# EEGAmp_SMT_MountHole.net
KiCad netlist of a schematic drawn in EAGLE
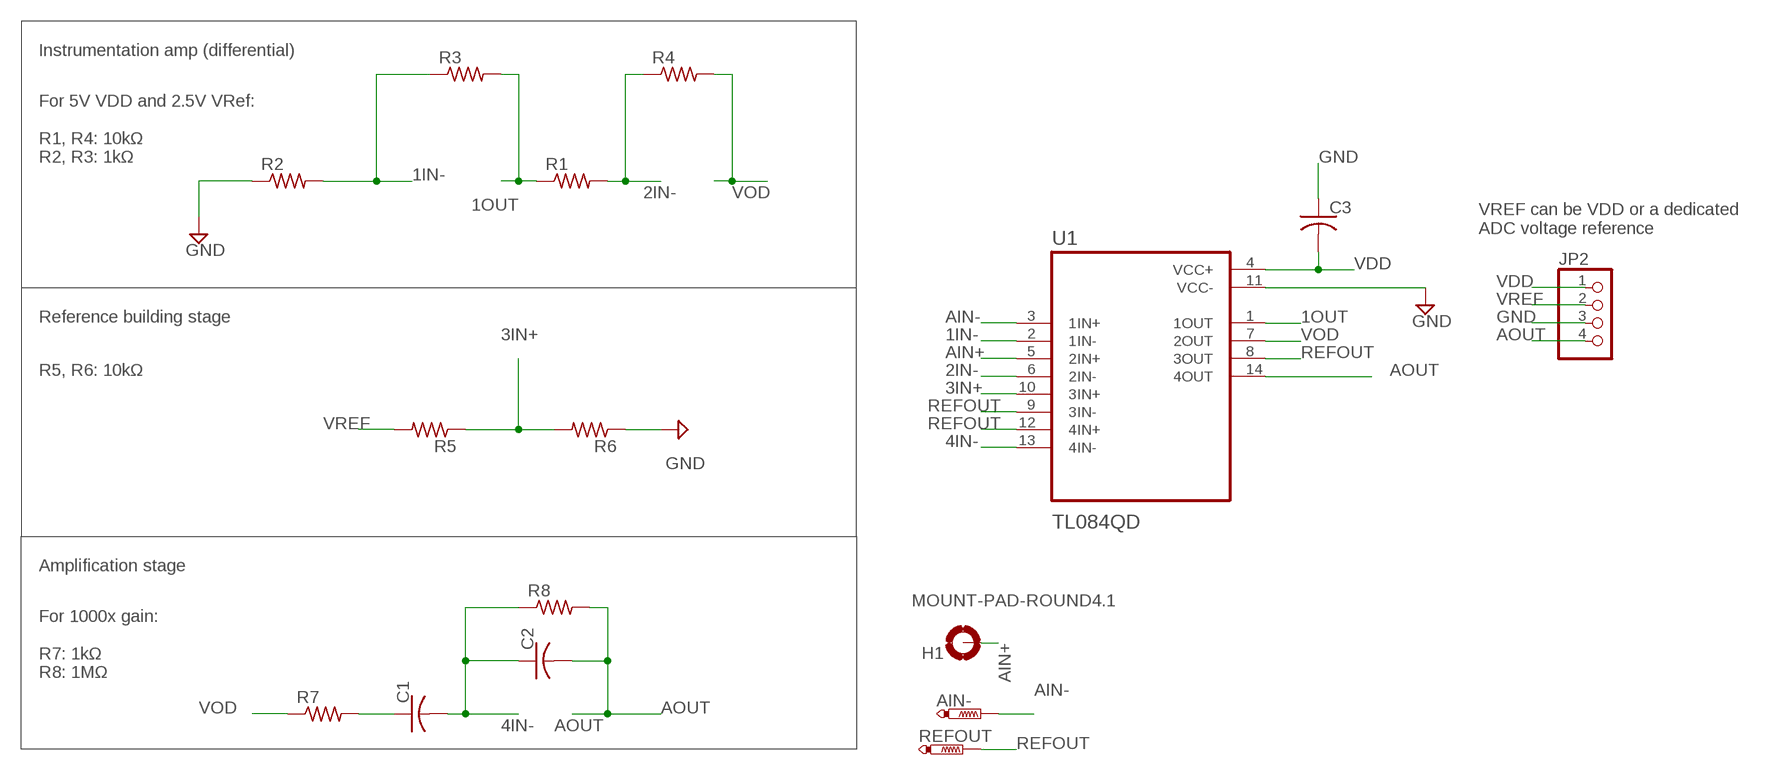
[diagram p0: schematic, sheet 1]

(export (version "E")
  (design (tool "Eeschema 10.0.6"))
  (components
    (comp (ref "AIN-")
      (value "PTR1PAD1-17")
      (footprint "eagle-import:P1-17")
      (libsource (lib "eagle-import") (part "PTR1PAD1-17"))
    )
    (comp (ref "C1")
      (value "C-USC0402")
      (footprint "eagle-import:C0402")
      (libsource (lib "eagle-import") (part "C-USC0402"))
    )
    (comp (ref "C2")
      (value "C-USC0402")
      (footprint "eagle-import:C0402")
      (libsource (lib "eagle-import") (part "C-USC0402"))
    )
    (comp (ref "C3")
      (value "C-USC0402")
      (footprint "eagle-import:C0402")
      (libsource (lib "eagle-import") (part "C-USC0402"))
    )
    (comp (ref "H1")
      (value "MOUNT-PAD-ROUND4.1")
      (footprint "eagle-import:4,1-PAD")
      (libsource (lib "eagle-import") (part "MOUNT-PAD-ROUND4.1"))
    )
    (comp (ref "JP2")
      (value "PINHD-1X4")
      (footprint "eagle-import:1X04")
      (libsource (lib "eagle-import") (part "PINHD-1X4"))
    )
    (comp (ref "R1")
      (value "R-US_R0402")
      (footprint "eagle-import:R0402")
      (libsource (lib "eagle-import") (part "R-US_R0402"))
    )
    (comp (ref "R2")
      (value "R-US_R0402")
      (footprint "eagle-import:R0402")
      (libsource (lib "eagle-import") (part "R-US_R0402"))
    )
    (comp (ref "R3")
      (value "R-US_R0402")
      (footprint "eagle-import:R0402")
      (libsource (lib "eagle-import") (part "R-US_R0402"))
    )
    (comp (ref "R4")
      (value "R-US_R0402")
      (footprint "eagle-import:R0402")
      (libsource (lib "eagle-import") (part "R-US_R0402"))
    )
    (comp (ref "R5")
      (value "R-US_R0402")
      (footprint "eagle-import:R0402")
      (libsource (lib "eagle-import") (part "R-US_R0402"))
    )
    (comp (ref "R6")
      (value "R-US_R0402")
      (footprint "eagle-import:R0402")
      (libsource (lib "eagle-import") (part "R-US_R0402"))
    )
    (comp (ref "R7")
      (value "R-US_R0402")
      (footprint "eagle-import:R0402")
      (libsource (lib "eagle-import") (part "R-US_R0402"))
    )
    (comp (ref "R8")
      (value "R-US_R0402")
      (footprint "eagle-import:R0402")
      (libsource (lib "eagle-import") (part "R-US_R0402"))
    )
    (comp (ref "REFOUT")
      (value "PTR1PAD1-17")
      (footprint "eagle-import:P1-17")
      (libsource (lib "eagle-import") (part "PTR1PAD1-17"))
    )
    (comp (ref "U1")
      (value "TL084QD")
      (footprint "eagle-import:SOIC127P600X175-14N")
      (fields (field (name "MF") "Texas Instruments"))
      (libsource (lib "eagle-import") (part "TL084QD"))
    )
  )
  (nets
    (net (code "1") (name "/1IN-") (class "Default")
      (node (ref "R2") (pin "2") (pinfunction "2_2") (pintype "passive"))
      (node (ref "R3") (pin "1") (pinfunction "1_1") (pintype "passive"))
      (node (ref "U1") (pin "2") (pinfunction "1IN-_2") (pintype "input"))
    )
    (net (code "2") (name "/1OUT") (class "Default")
      (node (ref "R1") (pin "1") (pinfunction "1_1") (pintype "passive"))
      (node (ref "R3") (pin "2") (pinfunction "2_2") (pintype "passive"))
      (node (ref "U1") (pin "1") (pinfunction "1OUT_1") (pintype "output"))
    )
    (net (code "3") (name "/2IN-") (class "Default")
      (node (ref "R1") (pin "2") (pinfunction "2_2") (pintype "passive"))
      (node (ref "R4") (pin "1") (pinfunction "1_1") (pintype "passive"))
      (node (ref "U1") (pin "6") (pinfunction "2IN-_6") (pintype "input"))
    )
    (net (code "4") (name "/3IN+") (class "Default")
      (node (ref "R5") (pin "1") (pinfunction "1_1") (pintype "passive"))
      (node (ref "R6") (pin "2") (pinfunction "2_2") (pintype "passive"))
      (node (ref "U1") (pin "10") (pinfunction "3IN+_10") (pintype "input"))
    )
    (net (code "5") (name "/4IN-") (class "Default")
      (node (ref "C1") (pin "2") (pinfunction "2_2") (pintype "passive"))
      (node (ref "C2") (pin "1") (pinfunction "1_1") (pintype "passive"))
      (node (ref "R8") (pin "1") (pinfunction "1_1") (pintype "passive"))
      (node (ref "U1") (pin "13") (pinfunction "4IN-_13") (pintype "input"))
    )
    (net (code "6") (name "/AIN+") (class "Default")
      (node (ref "H1") (pin "B4,1") (pinfunction "MOUNT_B4,1") (pintype "passive"))
      (node (ref "U1") (pin "5") (pinfunction "2IN+_5") (pintype "input"))
    )
    (net (code "7") (name "/AIN-") (class "Default")
      (node (ref "AIN-") (pin "TP") (pinfunction "TP_TP") (pintype "input"))
      (node (ref "U1") (pin "3") (pinfunction "1IN+_3") (pintype "input"))
    )
    (net (code "8") (name "/AOUT") (class "Default")
      (node (ref "C2") (pin "2") (pinfunction "2_2") (pintype "passive"))
      (node (ref "JP2") (pin "4") (pinfunction "4_4") (pintype "passive"))
      (node (ref "R8") (pin "2") (pinfunction "2_2") (pintype "passive"))
      (node (ref "U1") (pin "14") (pinfunction "4OUT_14") (pintype "output"))
    )
    (net (code "9") (name "/REFOUT") (class "Default")
      (node (ref "REFOUT") (pin "TP") (pinfunction "TP_TP") (pintype "input"))
      (node (ref "U1") (pin "12") (pinfunction "4IN+_12") (pintype "input"))
      (node (ref "U1") (pin "8") (pinfunction "3OUT_8") (pintype "output"))
      (node (ref "U1") (pin "9") (pinfunction "3IN-_9") (pintype "input"))
    )
    (net (code "10") (name "/VDD") (class "Default")
      (node (ref "C3") (pin "2") (pinfunction "2_2") (pintype "passive"))
      (node (ref "JP2") (pin "1") (pinfunction "1_1") (pintype "passive"))
      (node (ref "U1") (pin "4") (pinfunction "VCC+_4") (pintype "power_in"))
    )
    (net (code "11") (name "/VOD") (class "Default")
      (node (ref "R4") (pin "2") (pinfunction "2_2") (pintype "passive"))
      (node (ref "R7") (pin "1") (pinfunction "1_1") (pintype "passive"))
      (node (ref "U1") (pin "7") (pinfunction "2OUT_7") (pintype "output"))
    )
    (net (code "12") (name "/VREF") (class "Default")
      (node (ref "JP2") (pin "2") (pinfunction "2_2") (pintype "passive"))
      (node (ref "R5") (pin "2") (pinfunction "2_2") (pintype "passive"))
    )
    (net (code "13") (name "GND") (class "Default")
      (node (ref "C3") (pin "1") (pinfunction "1_1") (pintype "passive"))
      (node (ref "JP2") (pin "3") (pinfunction "3_3") (pintype "passive"))
      (node (ref "R2") (pin "1") (pinfunction "1_1") (pintype "passive"))
      (node (ref "R6") (pin "1") (pinfunction "1_1") (pintype "passive"))
      (node (ref "U1") (pin "11") (pinfunction "VCC-_11") (pintype "power_in"))
    )
    (net (code "14") (name "Net-(C1-Pad1)") (class "Default")
      (node (ref "C1") (pin "1") (pinfunction "1_1") (pintype "passive"))
      (node (ref "R7") (pin "2") (pinfunction "2_2") (pintype "passive"))
    )
  )
)
